# currentW_conditioning.net
KiCad netlist of a schematic drawn in Altium Designer
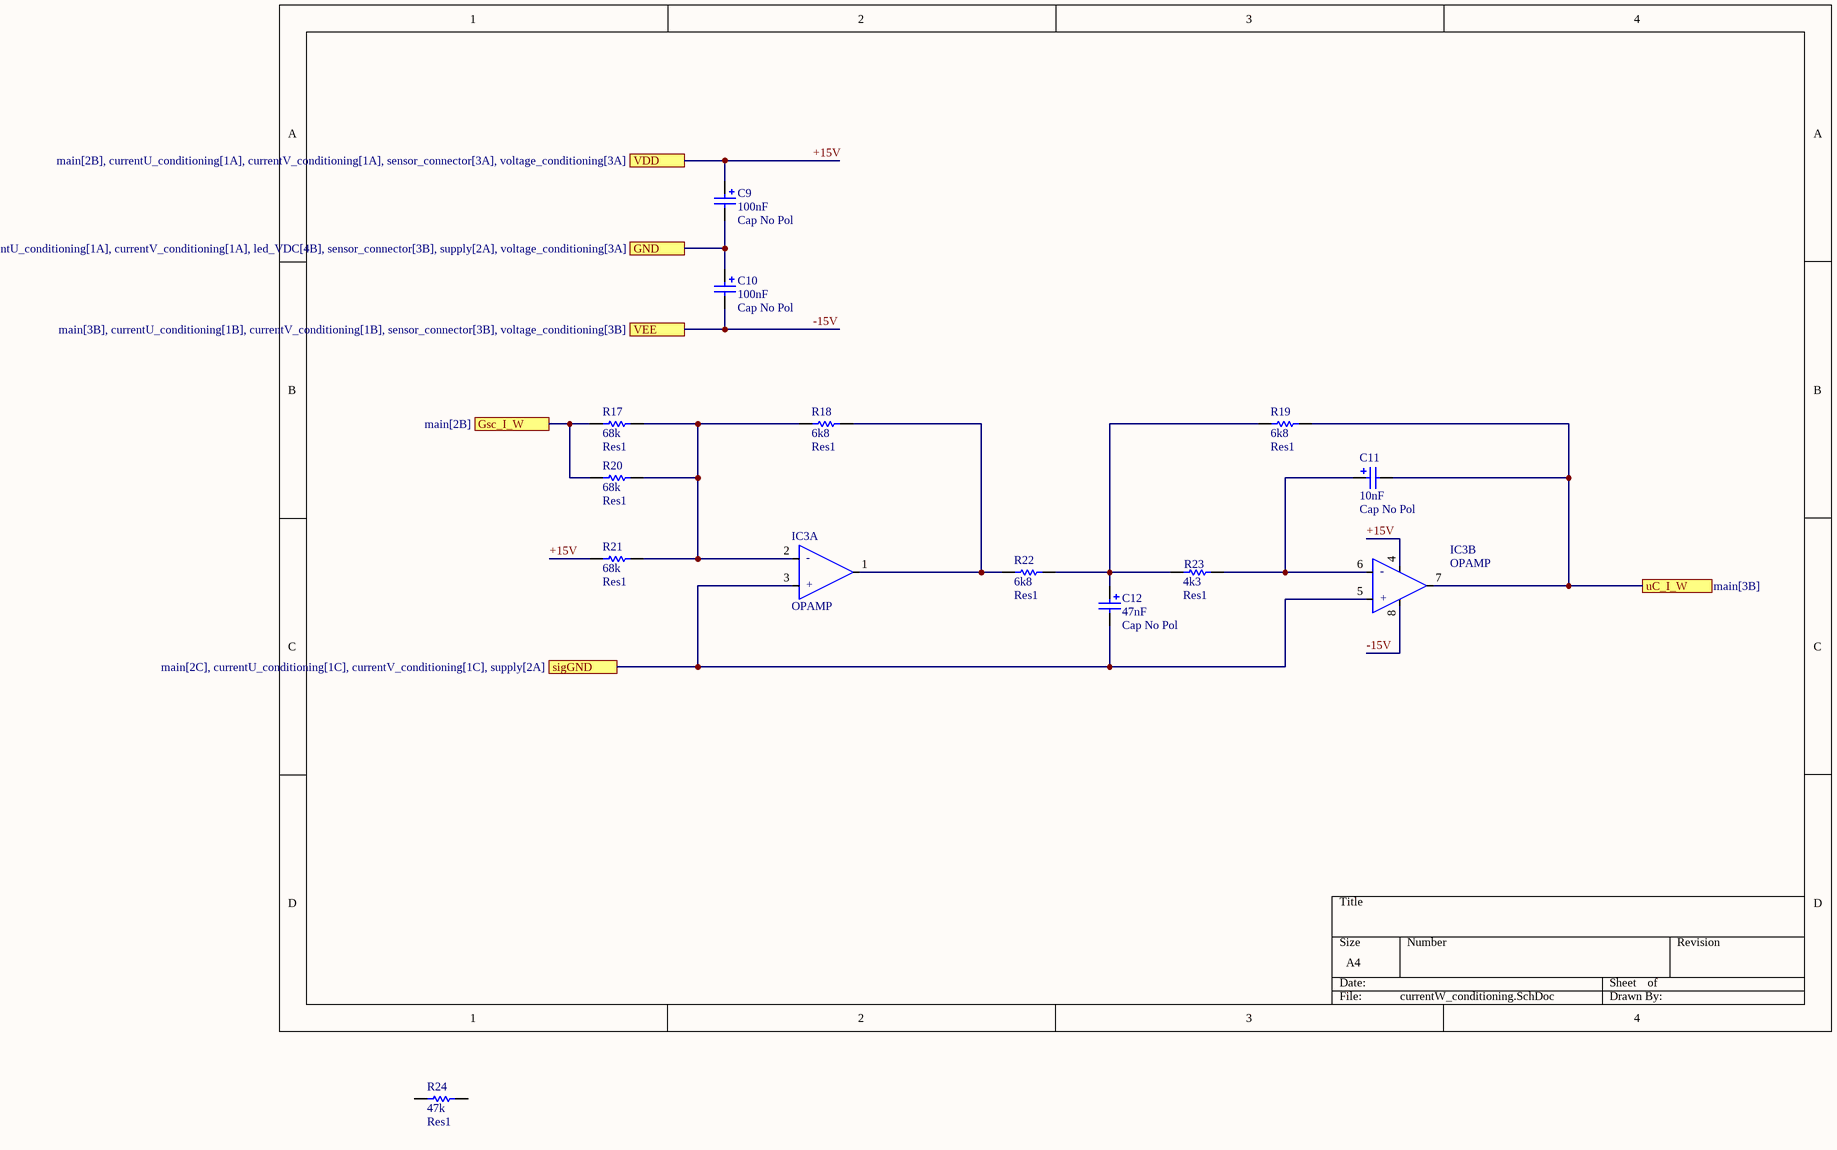
[diagram p0: currentW_conditioning.SchDoc]

(export (version "E")
  (design (tool "Eeschema 10.0.6"))
  (components
    (comp (ref "C9")
      (value "Cap No Pol")
      (footprint "RAD-0.1")
      (description "Polarized Capacitor (Radial)")
      (fields (field (name "ALTIUM_VALUE") "100nF") (field (name "PUBLISHER") "Altium Limited"))
      (libsource (lib "LABSTEPS_Project") (part "Cap No Pol"))
    )
    (comp (ref "C10")
      (value "Cap No Pol")
      (footprint "RAD-0.1")
      (description "Polarized Capacitor (Radial)")
      (fields (field (name "ALTIUM_VALUE") "100nF") (field (name "PUBLISHER") "Altium Limited"))
      (libsource (lib "LABSTEPS_Project") (part "Cap No Pol"))
    )
    (comp (ref "C11")
      (value "Cap No Pol")
      (footprint "RAD-0.1")
      (description "Polarized Capacitor (Radial)")
      (fields (field (name "ALTIUM_VALUE") "10nF") (field (name "PUBLISHER") "Altium Limited"))
      (libsource (lib "LABSTEPS_Project") (part "Cap No Pol"))
    )
    (comp (ref "C12")
      (value "Cap No Pol")
      (footprint "RAD-0.1")
      (description "Polarized Capacitor (Radial)")
      (fields (field (name "ALTIUM_VALUE") "47nF") (field (name "PUBLISHER") "Altium Limited"))
      (libsource (lib "LABSTEPS_Project") (part "Cap No Pol"))
    )
    (comp (ref "IC3")
      (value "OPAMP")
      (footprint "DIP-8")
      (description "ADTL082")
      (libsource (lib "LABSTEPS_Project") (part "ADTL082"))
    )
    (comp (ref "R17")
      (value "Res1")
      (footprint "AXIAL-0.3")
      (description "Resistor")
      (fields (field (name "ALTIUM_VALUE") "68k") (field (name "PUBLISHER") "Altium Limited"))
      (libsource (lib "LABSTEPS_Project") (part "Res1"))
    )
    (comp (ref "R18")
      (value "Res1")
      (footprint "AXIAL-0.3")
      (description "Resistor")
      (fields (field (name "ALTIUM_VALUE") "6k8") (field (name "PUBLISHER") "Altium Limited"))
      (libsource (lib "LABSTEPS_Project") (part "Res1"))
    )
    (comp (ref "R19")
      (value "Res1")
      (footprint "AXIAL-0.3")
      (description "Resistor")
      (fields (field (name "ALTIUM_VALUE") "6k8") (field (name "PUBLISHER") "Altium Limited"))
      (libsource (lib "LABSTEPS_Project") (part "Res1"))
    )
    (comp (ref "R20")
      (value "Res1")
      (footprint "AXIAL-0.3")
      (description "Resistor")
      (fields (field (name "ALTIUM_VALUE") "68k") (field (name "PUBLISHER") "Altium Limited"))
      (libsource (lib "LABSTEPS_Project") (part "Res1"))
    )
    (comp (ref "R21")
      (value "Res1")
      (footprint "AXIAL-0.3")
      (description "Resistor")
      (fields (field (name "ALTIUM_VALUE") "68k") (field (name "PUBLISHER") "Altium Limited"))
      (libsource (lib "LABSTEPS_Project") (part "Res1"))
    )
    (comp (ref "R22")
      (value "Res1")
      (footprint "AXIAL-0.3")
      (description "Resistor")
      (fields (field (name "ALTIUM_VALUE") "6k8") (field (name "PUBLISHER") "Altium Limited"))
      (libsource (lib "LABSTEPS_Project") (part "Res1"))
    )
    (comp (ref "R23")
      (value "Res1")
      (footprint "AXIAL-0.3")
      (description "Resistor")
      (fields (field (name "ALTIUM_VALUE") "4k3") (field (name "PUBLISHER") "Altium Limited"))
      (libsource (lib "LABSTEPS_Project") (part "Res1"))
    )
    (comp (ref "R24")
      (value "Res1")
      (footprint "AXIAL-0.3")
      (description "Resistor")
      (fields (field (name "ALTIUM_VALUE") "47k") (field (name "PUBLISHER") "Altium Limited"))
      (libsource (lib "LABSTEPS_Project") (part "Res1"))
    )
  )
  (nets
    (net (code "1") (name "/+15V") (class "Default")
      (node (ref "C9") (pin "1") (pinfunction "1_1") (pintype "passive"))
      (node (ref "IC3") (pin "4") (pinfunction "-V_4") (pintype "passive"))
      (node (ref "R21") (pin "1") (pinfunction "1_1") (pintype "passive"))
    )
    (net (code "2") (name "/-15V") (class "Default")
      (node (ref "C10") (pin "2") (pinfunction "2_2") (pintype "passive"))
      (node (ref "IC3") (pin "8") (pinfunction "V+_8") (pintype "passive"))
    )
    (net (code "3") (name "/GND") (class "Default")
      (node (ref "C10") (pin "1") (pinfunction "1_1") (pintype "passive"))
      (node (ref "C9") (pin "2") (pinfunction "2_2") (pintype "passive"))
    )
    (net (code "4") (name "/Gsc_I_W") (class "Default")
      (node (ref "R17") (pin "1") (pinfunction "1_1") (pintype "passive"))
      (node (ref "R20") (pin "1") (pinfunction "1_1") (pintype "passive"))
    )
    (net (code "5") (name "/sigGND") (class "Default")
      (node (ref "C12") (pin "2") (pinfunction "2_2") (pintype "passive"))
      (node (ref "IC3") (pin "3") (pinfunction "IN_A_+_3") (pintype "passive"))
      (node (ref "IC3") (pin "5") (pinfunction "IN_B_+_5") (pintype "passive"))
    )
    (net (code "6") (name "/uC_I_W") (class "Default")
      (node (ref "C11") (pin "2") (pinfunction "2_2") (pintype "passive"))
      (node (ref "IC3") (pin "7") (pinfunction "OUT_B_7") (pintype "passive"))
      (node (ref "R19") (pin "2") (pinfunction "2_2") (pintype "passive"))
    )
    (net (code "7") (name "Net-(C12-Pad1)") (class "Default")
      (node (ref "C12") (pin "1") (pinfunction "1_1") (pintype "passive"))
      (node (ref "R19") (pin "1") (pinfunction "1_1") (pintype "passive"))
      (node (ref "R22") (pin "2") (pinfunction "2_2") (pintype "passive"))
      (node (ref "R23") (pin "1") (pinfunction "1_1") (pintype "passive"))
    )
    (net (code "8") (name "Net-(IC3A-IN_A_-)") (class "Default")
      (node (ref "IC3") (pin "2") (pinfunction "IN_A_-_2") (pintype "passive"))
      (node (ref "R17") (pin "2") (pinfunction "2_2") (pintype "passive"))
      (node (ref "R18") (pin "1") (pinfunction "1_1") (pintype "passive"))
      (node (ref "R20") (pin "2") (pinfunction "2_2") (pintype "passive"))
      (node (ref "R21") (pin "2") (pinfunction "2_2") (pintype "passive"))
    )
    (net (code "9") (name "Net-(IC3A-OUT_A)") (class "Default")
      (node (ref "IC3") (pin "1") (pinfunction "OUT_A_1") (pintype "passive"))
      (node (ref "R18") (pin "2") (pinfunction "2_2") (pintype "passive"))
      (node (ref "R22") (pin "1") (pinfunction "1_1") (pintype "passive"))
    )
    (net (code "10") (name "Net-(IC3B-IN_B_-)") (class "Default")
      (node (ref "C11") (pin "1") (pinfunction "1_1") (pintype "passive"))
      (node (ref "IC3") (pin "6") (pinfunction "IN_B_-_6") (pintype "passive"))
      (node (ref "R23") (pin "2") (pinfunction "2_2") (pintype "passive"))
    )
    (net (code "11") (name "unconnected-(R24-Pad1)") (class "Default")
      (node (ref "R24") (pin "1") (pinfunction "1_1") (pintype "passive"))
    )
    (net (code "12") (name "unconnected-(R24-Pad2)") (class "Default")
      (node (ref "R24") (pin "2") (pinfunction "2_2") (pintype "passive"))
    )
  )
)
